# MySXSenors-VM02-002.net
KiCad netlist of a schematic drawn in EAGLE
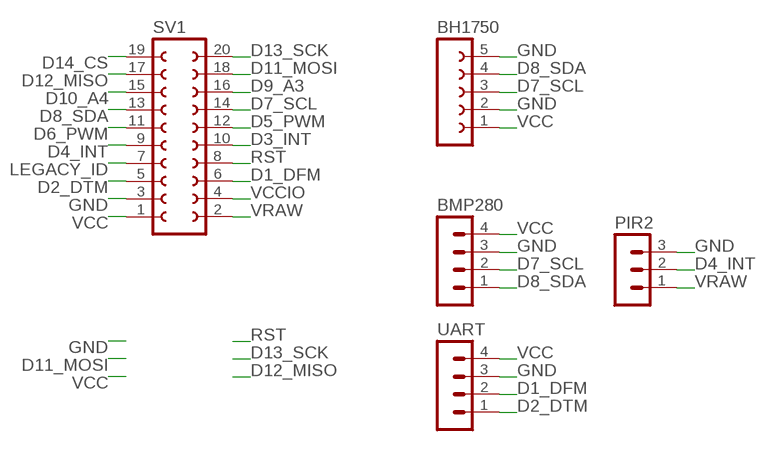
[diagram p0: schematic, sheet 1]

(export (version "E")
  (design (tool "Eeschema 10.0.6"))
  (components
    (comp (ref "BH1750")
      (value "FE05-1")
      (footprint "eagle-import:FE05-1")
      (libsource (lib "eagle-import") (part "FE05-1"))
    )
    (comp (ref "BMP280")
      (value "MA04-1")
      (footprint "eagle-import:MA04-1")
      (libsource (lib "eagle-import") (part "MA04-1"))
    )
    (comp (ref "PIR2")
      (value "MA03-1")
      (footprint "eagle-import:MA03-1")
      (libsource (lib "eagle-import") (part "MA03-1"))
    )
    (comp (ref "SV1")
      (value "FE10-2")
      (footprint "eagle-import:FE10-2")
      (libsource (lib "eagle-import") (part "FE10-2"))
    )
    (comp (ref "UART")
      (value "MA04-1")
      (footprint "eagle-import:MA04-1")
      (libsource (lib "eagle-import") (part "MA04-1"))
    )
  )
  (nets
    (net (code "1") (name "/D1_DFM") (class "Default")
      (node (ref "SV1") (pin "6") (pinfunction "6_6") (pintype "passive"))
      (node (ref "UART") (pin "2") (pinfunction "2_2") (pintype "passive"))
    )
    (net (code "2") (name "/D2_DTM") (class "Default")
      (node (ref "SV1") (pin "5") (pinfunction "5_5") (pintype "passive"))
      (node (ref "UART") (pin "1") (pinfunction "1_1") (pintype "passive"))
    )
    (net (code "3") (name "/D3_INT") (class "Default")
      (node (ref "SV1") (pin "10") (pinfunction "10_10") (pintype "passive"))
    )
    (net (code "4") (name "/D4_INT") (class "Default")
      (node (ref "PIR2") (pin "2") (pinfunction "2_2") (pintype "passive"))
      (node (ref "SV1") (pin "9") (pinfunction "9_9") (pintype "passive"))
    )
    (net (code "5") (name "/D5_PWM") (class "Default")
      (node (ref "SV1") (pin "12") (pinfunction "12_12") (pintype "passive"))
    )
    (net (code "6") (name "/D6_PWM") (class "Default")
      (node (ref "SV1") (pin "11") (pinfunction "11_11") (pintype "passive"))
    )
    (net (code "7") (name "/D7_SCL") (class "Default")
      (node (ref "BH1750") (pin "3") (pinfunction "3_3") (pintype "passive"))
      (node (ref "BMP280") (pin "2") (pinfunction "2_2") (pintype "passive"))
      (node (ref "SV1") (pin "14") (pinfunction "14_14") (pintype "passive"))
    )
    (net (code "8") (name "/D8_SDA") (class "Default")
      (node (ref "BH1750") (pin "4") (pinfunction "4_4") (pintype "passive"))
      (node (ref "BMP280") (pin "1") (pinfunction "1_1") (pintype "passive"))
      (node (ref "SV1") (pin "13") (pinfunction "13_13") (pintype "passive"))
    )
    (net (code "9") (name "/D9_A3") (class "Default")
      (node (ref "SV1") (pin "16") (pinfunction "16_16") (pintype "passive"))
    )
    (net (code "10") (name "/D10_A4") (class "Default")
      (node (ref "SV1") (pin "15") (pinfunction "15_15") (pintype "passive"))
    )
    (net (code "11") (name "/D11_MOSI") (class "Default")
      (node (ref "SV1") (pin "18") (pinfunction "18_18") (pintype "passive"))
    )
    (net (code "12") (name "/D12_MISO") (class "Default")
      (node (ref "SV1") (pin "17") (pinfunction "17_17") (pintype "passive"))
    )
    (net (code "13") (name "/D13_SCK") (class "Default")
      (node (ref "SV1") (pin "20") (pinfunction "20_20") (pintype "passive"))
    )
    (net (code "14") (name "/D14_CS") (class "Default")
      (node (ref "SV1") (pin "19") (pinfunction "19_19") (pintype "passive"))
    )
    (net (code "15") (name "/GND") (class "Default")
      (node (ref "BH1750") (pin "2") (pinfunction "2_2") (pintype "passive"))
      (node (ref "BH1750") (pin "5") (pinfunction "5_5") (pintype "passive"))
      (node (ref "BMP280") (pin "3") (pinfunction "3_3") (pintype "passive"))
      (node (ref "PIR2") (pin "3") (pinfunction "3_3") (pintype "passive"))
      (node (ref "SV1") (pin "3") (pinfunction "3_3") (pintype "passive"))
      (node (ref "UART") (pin "3") (pinfunction "3_3") (pintype "passive"))
    )
    (net (code "16") (name "/LEGACY_ID") (class "Default")
      (node (ref "SV1") (pin "7") (pinfunction "7_7") (pintype "passive"))
    )
    (net (code "17") (name "/RST") (class "Default")
      (node (ref "SV1") (pin "8") (pinfunction "8_8") (pintype "passive"))
    )
    (net (code "18") (name "/VCC") (class "Default")
      (node (ref "BH1750") (pin "1") (pinfunction "1_1") (pintype "passive"))
      (node (ref "BMP280") (pin "4") (pinfunction "4_4") (pintype "passive"))
      (node (ref "SV1") (pin "1") (pinfunction "1_1") (pintype "passive"))
      (node (ref "UART") (pin "4") (pinfunction "4_4") (pintype "passive"))
    )
    (net (code "19") (name "/VCCIO") (class "Default")
      (node (ref "SV1") (pin "4") (pinfunction "4_4") (pintype "passive"))
    )
    (net (code "20") (name "/VRAW") (class "Default")
      (node (ref "PIR2") (pin "1") (pinfunction "1_1") (pintype "passive"))
      (node (ref "SV1") (pin "2") (pinfunction "2_2") (pintype "passive"))
    )
  )
)
